# deadlock-reader.net
KiCad netlist of a schematic drawn in EAGLE
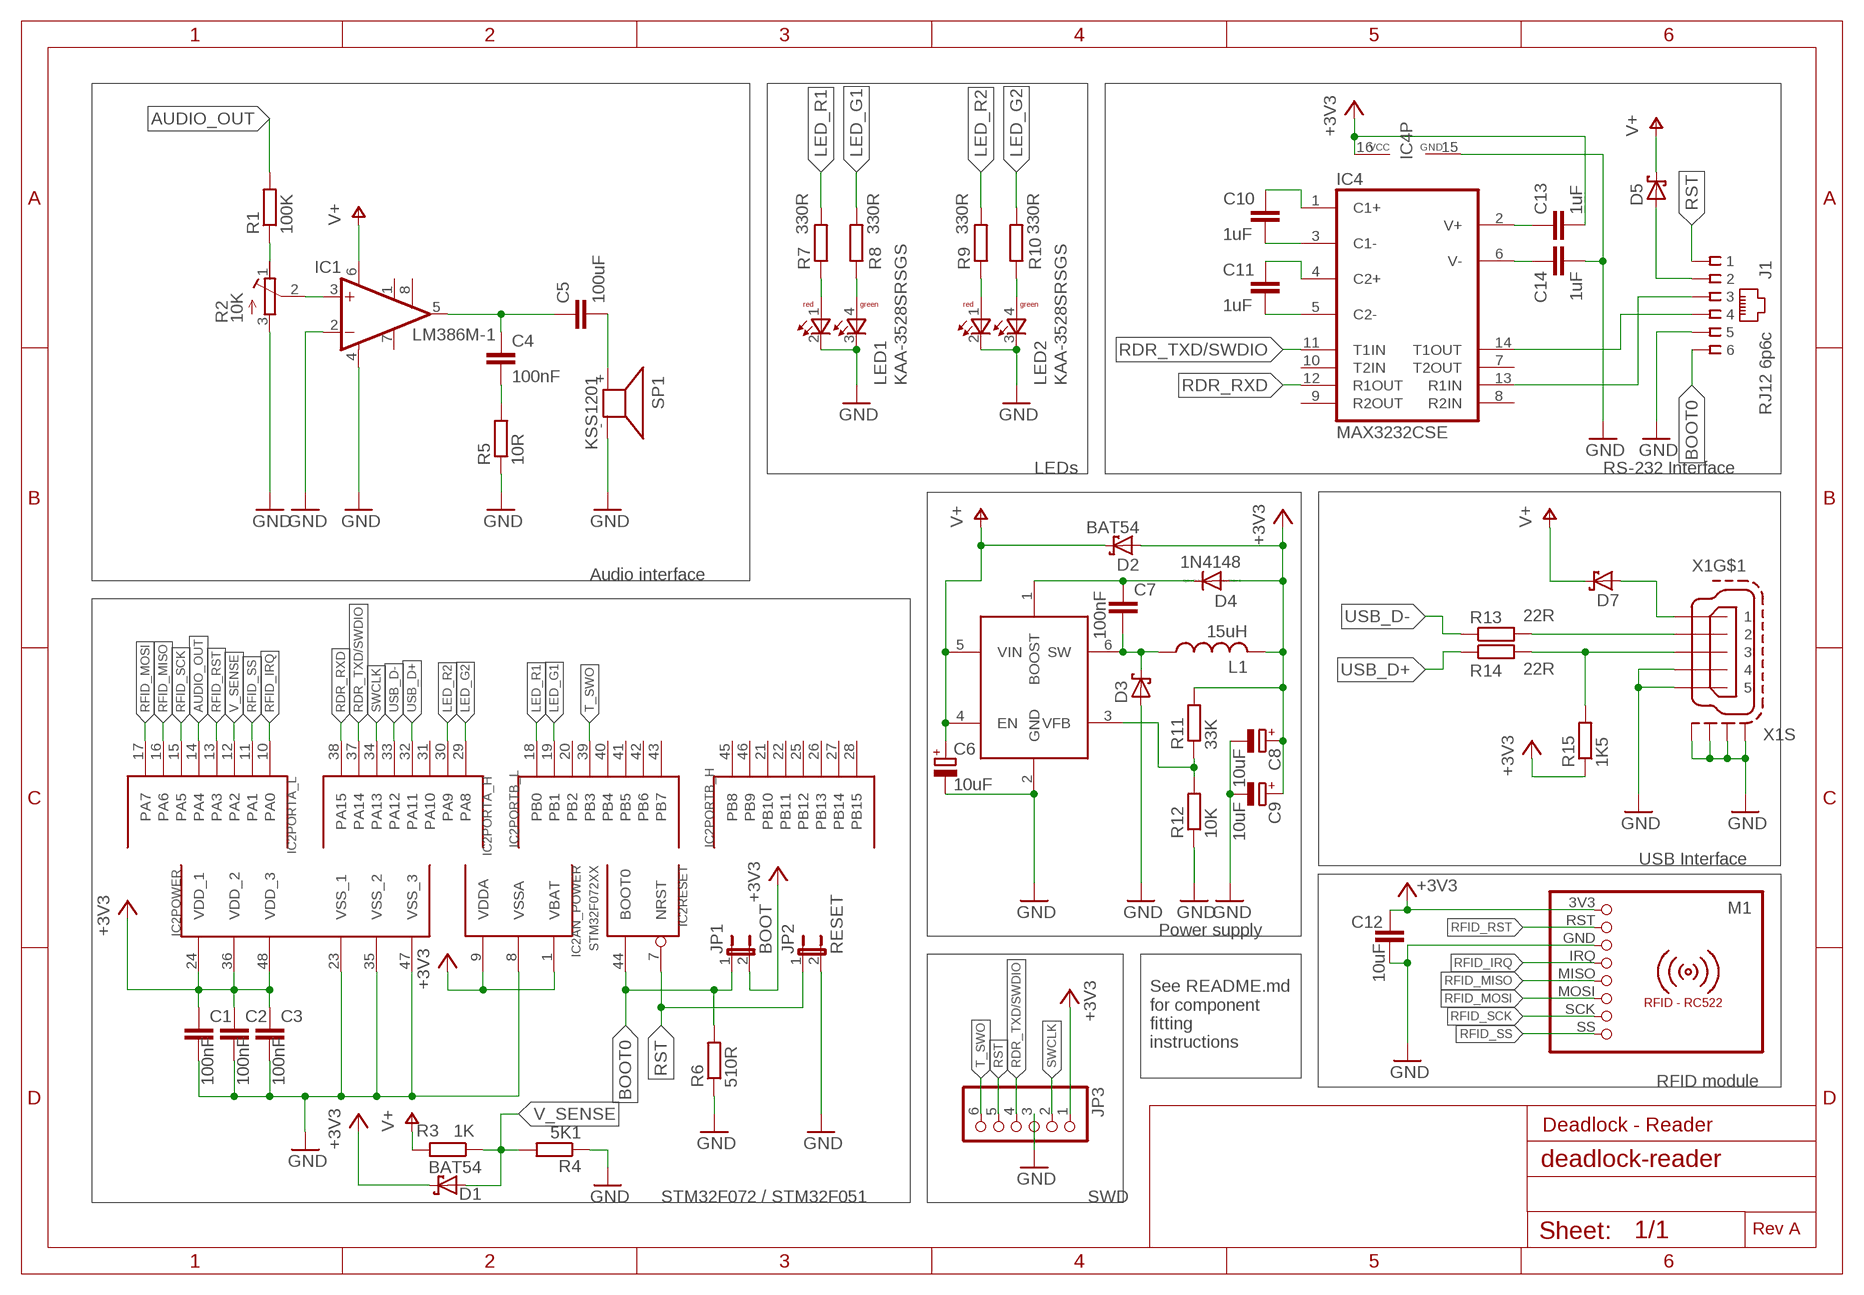
[diagram p0: schematic, sheet 1]

(export (version "E")
  (design (tool "Eeschema 10.0.6"))
  (components
    (comp (ref "C1")
      (value "100nF")
      (footprint "eagle-import:C0805")
      (libsource (lib "eagle-import") (part "C-EUC0805"))
    )
    (comp (ref "C2")
      (value "100nF")
      (footprint "eagle-import:C0805")
      (libsource (lib "eagle-import") (part "C-EUC0805"))
    )
    (comp (ref "C3")
      (value "100nF")
      (footprint "eagle-import:C0805")
      (libsource (lib "eagle-import") (part "C-EUC0805"))
    )
    (comp (ref "C4")
      (value "100nF")
      (footprint "eagle-import:C0805")
      (libsource (lib "eagle-import") (part "C-EUC0805"))
    )
    (comp (ref "C5")
      (value "100uF")
      (footprint "eagle-import:C1206")
      (libsource (lib "eagle-import") (part "C-EUC1206"))
    )
    (comp (ref "C6")
      (value "10uF")
      (footprint "eagle-import:SMC_D")
      (libsource (lib "eagle-import") (part "CPOL-EUSMCD"))
    )
    (comp (ref "C7")
      (value "100nF")
      (footprint "eagle-import:C0805")
      (libsource (lib "eagle-import") (part "C-EUC0805"))
    )
    (comp (ref "C8")
      (value "10uF")
      (footprint "eagle-import:A_3216-18R")
      (libsource (lib "eagle-import") (part "CPOL-EUA/3216-18R"))
    )
    (comp (ref "C9")
      (value "10uF")
      (footprint "eagle-import:A_3216-18R")
      (libsource (lib "eagle-import") (part "CPOL-EUA/3216-18R"))
    )
    (comp (ref "C10")
      (value "1uF")
      (footprint "eagle-import:C0805")
      (libsource (lib "eagle-import") (part "C-EUC0805"))
    )
    (comp (ref "C11")
      (value "1uF")
      (footprint "eagle-import:C0805")
      (libsource (lib "eagle-import") (part "C-EUC0805"))
    )
    (comp (ref "C12")
      (value "10uF")
      (footprint "eagle-import:C0805")
      (libsource (lib "eagle-import") (part "C-EUC0805"))
    )
    (comp (ref "C13")
      (value "1uF")
      (footprint "eagle-import:C0805")
      (libsource (lib "eagle-import") (part "C-EUC0805"))
    )
    (comp (ref "C14")
      (value "1uF")
      (footprint "eagle-import:C0805")
      (libsource (lib "eagle-import") (part "C-EUC0805"))
    )
    (comp (ref "D1")
      (value "BAT54")
      (footprint "eagle-import:SOT23")
      (libsource (lib "eagle-import") (part "BAT54"))
    )
    (comp (ref "D2")
      (value "BAT54")
      (footprint "eagle-import:SOT23")
      (libsource (lib "eagle-import") (part "BAT54"))
    )
    (comp (ref "D3")
      (value "BAT60J")
      (footprint "eagle-import:SOD323_ST")
      (libsource (lib "eagle-import") (part "BAT60J"))
    )
    (comp (ref "D4")
      (value "1N4148")
      (footprint "eagle-import:SOD323-W")
      (libsource (lib "eagle-import") (part "DIODE-SOD323-W"))
    )
    (comp (ref "D5")
      (value "BAT60J")
      (footprint "eagle-import:SOD323_ST")
      (libsource (lib "eagle-import") (part "BAT60J"))
    )
    (comp (ref "D7")
      (value "BAT60J")
      (footprint "eagle-import:SOD323_ST")
      (libsource (lib "eagle-import") (part "BAT60J"))
    )
    (comp (ref "IC1")
      (value "LM386M-1")
      (footprint "eagle-import:SO08")
      (libsource (lib "eagle-import") (part "LM386?-M1"))
    )
    (comp (ref "IC2")
      (value "STM32F072XX")
      (footprint "eagle-import:TQFP48")
      (libsource (lib "eagle-import") (part "STM32F072XX"))
    )
    (comp (ref "IC3")
      (value "MCP16301/H")
      (footprint "eagle-import:SOT23-6")
      (libsource (lib "eagle-import") (part "MCP16301/H"))
    )
    (comp (ref "IC4")
      (value "MAX3232CSE")
      (footprint "eagle-import:SO16")
      (libsource (lib "eagle-import") (part "MAX3232SEC"))
    )
    (comp (ref "J1")
      (value "RJ12 6p6c")
      (footprint "eagle-import:RJ11-NO_SHIELD")
      (libsource (lib "eagle-import") (part "RJ11-2X"))
    )
    (comp (ref "JP1")
      (value "BOOT")
      (footprint "eagle-import:JP1")
      (libsource (lib "eagle-import") (part "JP1E"))
    )
    (comp (ref "JP2")
      (value "RESET")
      (footprint "eagle-import:JP1")
      (libsource (lib "eagle-import") (part "JP1E"))
    )
    (comp (ref "JP3")
      (value "PINHD-1X6")
      (footprint "eagle-import:1X06")
      (libsource (lib "eagle-import") (part "PINHD-1X6"))
    )
    (comp (ref "L1")
      (value "15uH")
      (footprint "eagle-import:PIS2816")
      (libsource (lib "eagle-import") (part "L-USPIS2816"))
    )
    (comp (ref "LED1")
      (value "KAA-3528SRSGS")
      (footprint "eagle-import:KAA-3528SRSGS")
      (libsource (lib "eagle-import") (part "KAA-3528SRSGS"))
    )
    (comp (ref "LED2")
      (value "KAA-3528SRSGS")
      (footprint "eagle-import:KAA-3528SRSGS")
      (libsource (lib "eagle-import") (part "KAA-3528SRSGS"))
    )
    (comp (ref "M1")
      (value "RFID-RC522")
      (footprint "eagle-import:RFID-RC522")
      (libsource (lib "eagle-import") (part "RFID-RC522"))
    )
    (comp (ref "R1")
      (value "100K")
      (footprint "eagle-import:M0805")
      (libsource (lib "eagle-import") (part "resistor_R-EU_M0805"))
    )
    (comp (ref "R2")
      (value "10K")
      (footprint "eagle-import:RTRIM3314G")
      (libsource (lib "eagle-import") (part "R-TRIMM3314G"))
    )
    (comp (ref "R3")
      (value "1K")
      (footprint "eagle-import:R0805")
      (libsource (lib "eagle-import") (part "R-EU_R0805"))
    )
    (comp (ref "R4")
      (value "5K1")
      (footprint "eagle-import:R0805")
      (libsource (lib "eagle-import") (part "R-EU_R0805"))
    )
    (comp (ref "R5")
      (value "10R")
      (footprint "eagle-import:R0805")
      (libsource (lib "eagle-import") (part "R-EU_R0805"))
    )
    (comp (ref "R6")
      (value "510R")
      (footprint "eagle-import:R0805")
      (libsource (lib "eagle-import") (part "R-EU_R0805"))
    )
    (comp (ref "R7")
      (value "330R")
      (footprint "eagle-import:R0805")
      (libsource (lib "eagle-import") (part "R-EU_R0805"))
    )
    (comp (ref "R8")
      (value "330R")
      (footprint "eagle-import:R0805")
      (libsource (lib "eagle-import") (part "R-EU_R0805"))
    )
    (comp (ref "R9")
      (value "330R")
      (footprint "eagle-import:R0805")
      (libsource (lib "eagle-import") (part "R-EU_R0805"))
    )
    (comp (ref "R10")
      (value "330R")
      (footprint "eagle-import:R0805")
      (libsource (lib "eagle-import") (part "R-EU_R0805"))
    )
    (comp (ref "R11")
      (value "33K")
      (footprint "eagle-import:R0805")
      (libsource (lib "eagle-import") (part "R-EU_R0805"))
    )
    (comp (ref "R12")
      (value "10K")
      (footprint "eagle-import:R0805")
      (libsource (lib "eagle-import") (part "R-EU_R0805"))
    )
    (comp (ref "R13")
      (value "22R")
      (footprint "eagle-import:R0805")
      (libsource (lib "eagle-import") (part "R-EU_R0805"))
    )
    (comp (ref "R14")
      (value "22R")
      (footprint "eagle-import:R0805")
      (libsource (lib "eagle-import") (part "R-EU_R0805"))
    )
    (comp (ref "R15")
      (value "1K5")
      (footprint "eagle-import:R0805")
      (libsource (lib "eagle-import") (part "R-EU_R0805"))
    )
    (comp (ref "SP1")
      (value "KSS1201")
      (footprint "eagle-import:KSS1201")
      (libsource (lib "eagle-import") (part "KSS1201"))
    )
    (comp (ref "X1")
      (value "MINI-USB-SCHIELD-32005-301")
      (footprint "eagle-import:32005-301")
      (libsource (lib "eagle-import") (part "MINI-USB-SCHIELD-32005-301"))
    )
  )
  (nets
    (net (code "1") (name "+3V3") (class "Default")
      (node (ref "C1") (pin "1") (pinfunction "1_1") (pintype "passive"))
      (node (ref "C12") (pin "1") (pinfunction "1_1") (pintype "passive"))
      (node (ref "C13") (pin "2") (pinfunction "2_2") (pintype "passive"))
      (node (ref "C2") (pin "1") (pinfunction "1_1") (pintype "passive"))
      (node (ref "C3") (pin "1") (pinfunction "1_1") (pintype "passive"))
      (node (ref "C8") (pin "+") (pinfunction "+_+") (pintype "passive"))
      (node (ref "C9") (pin "+") (pinfunction "+_+") (pintype "passive"))
      (node (ref "D1") (pin "3") (pinfunction "C_3") (pintype "passive"))
      (node (ref "D2") (pin "1") (pinfunction "A_1") (pintype "passive"))
      (node (ref "D4") (pin "A") (pinfunction "A_A") (pintype "passive"))
      (node (ref "IC2") (pin "1") (pinfunction "VBAT_1") (pintype "power_in"))
      (node (ref "IC2") (pin "24") (pinfunction "VDD_1_24") (pintype "power_in"))
      (node (ref "IC2") (pin "36") (pinfunction "VDD_2_36") (pintype "power_in"))
      (node (ref "IC2") (pin "48") (pinfunction "VDD_3_48") (pintype "power_in"))
      (node (ref "IC2") (pin "9") (pinfunction "VDDA_9") (pintype "power_in"))
      (node (ref "IC4") (pin "16") (pinfunction "VCC_16") (pintype "power_in"))
      (node (ref "JP1") (pin "2") (pinfunction "2_2") (pintype "passive"))
      (node (ref "JP3") (pin "1") (pinfunction "1_1") (pintype "passive"))
      (node (ref "L1") (pin "2") (pinfunction "2_2") (pintype "passive"))
      (node (ref "M1") (pin "3V3") (pinfunction "1_3V3") (pintype "passive"))
      (node (ref "R11") (pin "2") (pinfunction "2_2") (pintype "passive"))
      (node (ref "R15") (pin "1") (pinfunction "1_1") (pintype "passive"))
    )
    (net (code "2") (name "AUDIO_OUT") (class "Default")
      (node (ref "IC2") (pin "14") (pinfunction "PA4_14") (pintype "bidirectional"))
      (node (ref "R1") (pin "2") (pinfunction "2_2") (pintype "passive"))
    )
    (net (code "3") (name "BOOT0") (class "Default")
      (node (ref "IC2") (pin "44") (pinfunction "BOOT0_44") (pintype "input"))
      (node (ref "J1") (pin "6") (pinfunction "6_6") (pintype "passive"))
      (node (ref "JP1") (pin "1") (pinfunction "1_1") (pintype "passive"))
      (node (ref "R6") (pin "2") (pinfunction "2_2") (pintype "passive"))
    )
    (net (code "4") (name "GND") (class "Default")
      (node (ref "C1") (pin "2") (pinfunction "2_2") (pintype "passive"))
      (node (ref "C12") (pin "2") (pinfunction "2_2") (pintype "passive"))
      (node (ref "C14") (pin "2") (pinfunction "2_2") (pintype "passive"))
      (node (ref "C2") (pin "2") (pinfunction "2_2") (pintype "passive"))
      (node (ref "C3") (pin "2") (pinfunction "2_2") (pintype "passive"))
      (node (ref "C6") (pin "-") (pinfunction "-_-") (pintype "passive"))
      (node (ref "C8") (pin "-") (pinfunction "-_-") (pintype "passive"))
      (node (ref "C9") (pin "-") (pinfunction "-_-") (pintype "passive"))
      (node (ref "D3") (pin "A") (pinfunction "A_A") (pintype "passive"))
      (node (ref "IC1") (pin "2") (pinfunction "-IN_2") (pintype "input"))
      (node (ref "IC1") (pin "4") (pinfunction "GND_4") (pintype "power_in"))
      (node (ref "IC2") (pin "23") (pinfunction "VSS_1_23") (pintype "power_in"))
      (node (ref "IC2") (pin "35") (pinfunction "VSS_2_35") (pintype "power_in"))
      (node (ref "IC2") (pin "47") (pinfunction "VSS_3_47") (pintype "power_in"))
      (node (ref "IC2") (pin "8") (pinfunction "VSSA_8") (pintype "power_in"))
      (node (ref "IC3") (pin "2") (pinfunction "GND_2") (pintype "power_in"))
      (node (ref "IC4") (pin "15") (pinfunction "GND_15") (pintype "power_in"))
      (node (ref "J1") (pin "5") (pinfunction "5_5") (pintype "passive"))
      (node (ref "JP2") (pin "2") (pinfunction "2_2") (pintype "passive"))
      (node (ref "JP3") (pin "3") (pinfunction "3_3") (pintype "passive"))
      (node (ref "LED1") (pin "2") (pinfunction "C-RED_2") (pintype "passive"))
      (node (ref "LED1") (pin "3") (pinfunction "C-GREEN_3") (pintype "passive"))
      (node (ref "LED2") (pin "2") (pinfunction "C-RED_2") (pintype "passive"))
      (node (ref "LED2") (pin "3") (pinfunction "C-GREEN_3") (pintype "passive"))
      (node (ref "M1") (pin "GND") (pinfunction "3_GND") (pintype "passive"))
      (node (ref "R12") (pin "1") (pinfunction "1_1") (pintype "passive"))
      (node (ref "R2") (pin "3") (pinfunction "A_3") (pintype "passive"))
      (node (ref "R4") (pin "1") (pinfunction "1_1") (pintype "passive"))
      (node (ref "R5") (pin "1") (pinfunction "1_1") (pintype "passive"))
      (node (ref "R6") (pin "1") (pinfunction "1_1") (pintype "passive"))
      (node (ref "SP1") (pin "-") (pinfunction "2_-") (pintype "passive"))
      (node (ref "X1") (pin "4") (pinfunction "4_4") (pintype "passive"))
      (node (ref "X1") (pin "5") (pinfunction "5_5") (pintype "passive"))
      (node (ref "X1") (pin "M1") (pinfunction "S1_M1") (pintype "passive"))
      (node (ref "X1") (pin "M2") (pinfunction "S2_M2") (pintype "passive"))
      (node (ref "X1") (pin "M3") (pinfunction "S3_M3") (pintype "passive"))
      (node (ref "X1") (pin "M4") (pinfunction "S4_M4") (pintype "passive"))
    )
    (net (code "5") (name "LED_G1") (class "Default")
      (node (ref "IC2") (pin "19") (pinfunction "PB1_19") (pintype "bidirectional"))
      (node (ref "R8") (pin "2") (pinfunction "2_2") (pintype "passive"))
    )
    (net (code "6") (name "LED_G2") (class "Default")
      (node (ref "IC2") (pin "29") (pinfunction "PA8_29") (pintype "bidirectional"))
      (node (ref "R10") (pin "2") (pinfunction "2_2") (pintype "passive"))
    )
    (net (code "7") (name "LED_R1") (class "Default")
      (node (ref "IC2") (pin "18") (pinfunction "PB0_18") (pintype "bidirectional"))
      (node (ref "R7") (pin "2") (pinfunction "2_2") (pintype "passive"))
    )
    (net (code "8") (name "LED_R2") (class "Default")
      (node (ref "IC2") (pin "30") (pinfunction "PA9_30") (pintype "bidirectional"))
      (node (ref "R9") (pin "2") (pinfunction "2_2") (pintype "passive"))
    )
    (net (code "9") (name "Net-(C4-Pad2)") (class "Default")
      (node (ref "C4") (pin "2") (pinfunction "2_2") (pintype "passive"))
      (node (ref "R5") (pin "2") (pinfunction "2_2") (pintype "passive"))
    )
    (net (code "10") (name "Net-(D5-PadA)") (class "Default")
      (node (ref "D5") (pin "A") (pinfunction "A_A") (pintype "passive"))
      (node (ref "J1") (pin "2") (pinfunction "2_2") (pintype "passive"))
    )
    (net (code "11") (name "Net-(D7-PadA)") (class "Default")
      (node (ref "D7") (pin "A") (pinfunction "A_A") (pintype "passive"))
      (node (ref "X1") (pin "1") (pinfunction "1_1") (pintype "passive"))
    )
    (net (code "12") (name "Net-(IC1-+IN)") (class "Default")
      (node (ref "IC1") (pin "3") (pinfunction "+IN_3") (pintype "input"))
      (node (ref "R2") (pin "2") (pinfunction "S_2") (pintype "passive"))
    )
    (net (code "13") (name "Net-(IC1-OUT)") (class "Default")
      (node (ref "C4") (pin "1") (pinfunction "1_1") (pintype "passive"))
      (node (ref "C5") (pin "1") (pinfunction "1_1") (pintype "passive"))
      (node (ref "IC1") (pin "5") (pinfunction "OUT_5") (pintype "output"))
    )
    (net (code "14") (name "Net-(IC3-BOOST)") (class "Default")
      (node (ref "C7") (pin "1") (pinfunction "1_1") (pintype "passive"))
      (node (ref "D4") (pin "C") (pinfunction "C_C") (pintype "passive"))
      (node (ref "IC3") (pin "1") (pinfunction "BOOST_1") (pintype "bidirectional"))
    )
    (net (code "15") (name "Net-(IC3-SW)") (class "Default")
      (node (ref "C7") (pin "2") (pinfunction "2_2") (pintype "passive"))
      (node (ref "D3") (pin "C") (pinfunction "C_C") (pintype "passive"))
      (node (ref "IC3") (pin "6") (pinfunction "SW_6") (pintype "power_in"))
      (node (ref "L1") (pin "1") (pinfunction "1_1") (pintype "passive"))
    )
    (net (code "16") (name "Net-(IC3-VFB)") (class "Default")
      (node (ref "IC3") (pin "3") (pinfunction "VFB_3") (pintype "bidirectional"))
      (node (ref "R11") (pin "1") (pinfunction "1_1") (pintype "passive"))
      (node (ref "R12") (pin "2") (pinfunction "2_2") (pintype "passive"))
    )
    (net (code "17") (name "Net-(IC4A-C1+)") (class "Default")
      (node (ref "C10") (pin "1") (pinfunction "1_1") (pintype "passive"))
      (node (ref "IC4") (pin "1") (pinfunction "C1+_1") (pintype "bidirectional"))
    )
    (net (code "18") (name "Net-(IC4A-C1-)") (class "Default")
      (node (ref "C10") (pin "2") (pinfunction "2_2") (pintype "passive"))
      (node (ref "IC4") (pin "3") (pinfunction "C1-_3") (pintype "bidirectional"))
    )
    (net (code "19") (name "Net-(IC4A-C2+)") (class "Default")
      (node (ref "C11") (pin "1") (pinfunction "1_1") (pintype "passive"))
      (node (ref "IC4") (pin "4") (pinfunction "C2+_4") (pintype "bidirectional"))
    )
    (net (code "20") (name "Net-(IC4A-C2-)") (class "Default")
      (node (ref "C11") (pin "2") (pinfunction "2_2") (pintype "passive"))
      (node (ref "IC4") (pin "5") (pinfunction "C2-_5") (pintype "bidirectional"))
    )
    (net (code "21") (name "Net-(IC4A-R1IN)") (class "Default")
      (node (ref "IC4") (pin "13") (pinfunction "R1IN_13") (pintype "input"))
      (node (ref "J1") (pin "3") (pinfunction "3_3") (pintype "passive"))
    )
    (net (code "22") (name "Net-(IC4A-T1OUT)") (class "Default")
      (node (ref "IC4") (pin "14") (pinfunction "T1OUT_14") (pintype "output"))
      (node (ref "J1") (pin "4") (pinfunction "4_4") (pintype "passive"))
    )
    (net (code "23") (name "Net-(IC4A-V+)") (class "Default")
      (node (ref "C13") (pin "1") (pinfunction "1_1") (pintype "passive"))
      (node (ref "IC4") (pin "2") (pinfunction "V+_2") (pintype "bidirectional"))
    )
    (net (code "24") (name "Net-(IC4A-V-)") (class "Default")
      (node (ref "C14") (pin "1") (pinfunction "1_1") (pintype "passive"))
      (node (ref "IC4") (pin "6") (pinfunction "V-_6") (pintype "bidirectional"))
    )
    (net (code "25") (name "Net-(LED1-A-GREEN)") (class "Default")
      (node (ref "LED1") (pin "4") (pinfunction "A-GREEN_4") (pintype "passive"))
      (node (ref "R8") (pin "1") (pinfunction "1_1") (pintype "passive"))
    )
    (net (code "26") (name "Net-(LED1-A-RED)") (class "Default")
      (node (ref "LED1") (pin "1") (pinfunction "A-RED_1") (pintype "passive"))
      (node (ref "R7") (pin "1") (pinfunction "1_1") (pintype "passive"))
    )
    (net (code "27") (name "Net-(LED2-A-GREEN)") (class "Default")
      (node (ref "LED2") (pin "4") (pinfunction "A-GREEN_4") (pintype "passive"))
      (node (ref "R10") (pin "1") (pinfunction "1_1") (pintype "passive"))
    )
    (net (code "28") (name "Net-(LED2-A-RED)") (class "Default")
      (node (ref "LED2") (pin "1") (pinfunction "A-RED_1") (pintype "passive"))
      (node (ref "R9") (pin "1") (pinfunction "1_1") (pintype "passive"))
    )
    (net (code "29") (name "Net-(R2-E)") (class "Default")
      (node (ref "R1") (pin "1") (pinfunction "1_1") (pintype "passive"))
      (node (ref "R2") (pin "1") (pinfunction "E_1") (pintype "passive"))
    )
    (net (code "30") (name "Net-(R13-Pad2)") (class "Default")
      (node (ref "R13") (pin "2") (pinfunction "2_2") (pintype "passive"))
      (node (ref "X1") (pin "2") (pinfunction "2_2") (pintype "passive"))
    )
    (net (code "31") (name "Net-(R14-Pad2)") (class "Default")
      (node (ref "R14") (pin "2") (pinfunction "2_2") (pintype "passive"))
      (node (ref "R15") (pin "2") (pinfunction "2_2") (pintype "passive"))
      (node (ref "X1") (pin "3") (pinfunction "3_3") (pintype "passive"))
    )
    (net (code "32") (name "Net-(SP1-1)") (class "Default")
      (node (ref "C5") (pin "2") (pinfunction "2_2") (pintype "passive"))
      (node (ref "SP1") (pin "+") (pinfunction "1_+") (pintype "passive"))
    )
    (net (code "33") (name "RDR_RXD") (class "Default")
      (node (ref "IC2") (pin "38") (pinfunction "PA15_38") (pintype "bidirectional"))
      (node (ref "IC4") (pin "12") (pinfunction "R1OUT_12") (pintype "output"))
    )
    (net (code "34") (name "RDR_TXD{slash}SWDIO") (class "Default")
      (node (ref "IC2") (pin "37") (pinfunction "PA14_37") (pintype "bidirectional"))
      (node (ref "IC4") (pin "11") (pinfunction "T1IN_11") (pintype "input"))
      (node (ref "JP3") (pin "4") (pinfunction "4_4") (pintype "passive"))
    )
    (net (code "35") (name "RFID_IRQ") (class "Default")
      (node (ref "IC2") (pin "10") (pinfunction "PA0_10") (pintype "bidirectional"))
      (node (ref "M1") (pin "IRQ") (pinfunction "4_IRQ") (pintype "passive"))
    )
    (net (code "36") (name "RFID_MISO") (class "Default")
      (node (ref "IC2") (pin "16") (pinfunction "PA6_16") (pintype "bidirectional"))
      (node (ref "M1") (pin "MISO") (pinfunction "5_MISO") (pintype "passive"))
    )
    (net (code "37") (name "RFID_MOSI") (class "Default")
      (node (ref "IC2") (pin "17") (pinfunction "PA7_17") (pintype "bidirectional"))
      (node (ref "M1") (pin "MOSI") (pinfunction "6_MOSI") (pintype "passive"))
    )
    (net (code "38") (name "RFID_RST") (class "Default")
      (node (ref "IC2") (pin "13") (pinfunction "PA3_13") (pintype "bidirectional"))
      (node (ref "M1") (pin "RST") (pinfunction "2_RST") (pintype "passive"))
    )
    (net (code "39") (name "RFID_SCK") (class "Default")
      (node (ref "IC2") (pin "15") (pinfunction "PA5_15") (pintype "bidirectional"))
      (node (ref "M1") (pin "SCK") (pinfunction "7_SCK") (pintype "passive"))
    )
    (net (code "40") (name "RFID_SS") (class "Default")
      (node (ref "IC2") (pin "11") (pinfunction "PA1_11") (pintype "bidirectional"))
      (node (ref "M1") (pin "SS") (pinfunction "8_SS") (pintype "passive"))
    )
    (net (code "41") (name "RST") (class "Default")
      (node (ref "IC2") (pin "7") (pinfunction "NRST_7") (pintype "input"))
      (node (ref "J1") (pin "1") (pinfunction "1_1") (pintype "passive"))
      (node (ref "JP2") (pin "1") (pinfunction "1_1") (pintype "passive"))
      (node (ref "JP3") (pin "5") (pinfunction "5_5") (pintype "passive"))
    )
    (net (code "42") (name "SWCLK") (class "Default")
      (node (ref "IC2") (pin "34") (pinfunction "PA13_34") (pintype "bidirectional"))
      (node (ref "JP3") (pin "2") (pinfunction "2_2") (pintype "passive"))
    )
    (net (code "43") (name "T_SWO") (class "Default")
      (node (ref "IC2") (pin "39") (pinfunction "PB3_39") (pintype "bidirectional"))
      (node (ref "JP3") (pin "6") (pinfunction "6_6") (pintype "passive"))
    )
    (net (code "44") (name "USB_D+") (class "Default")
      (node (ref "IC2") (pin "32") (pinfunction "PA11_32") (pintype "bidirectional"))
      (node (ref "R14") (pin "1") (pinfunction "1_1") (pintype "passive"))
    )
    (net (code "45") (name "USB_D-") (class "Default")
      (node (ref "IC2") (pin "33") (pinfunction "PA12_33") (pintype "bidirectional"))
      (node (ref "R13") (pin "1") (pinfunction "1_1") (pintype "passive"))
    )
    (net (code "46") (name "V+") (class "Default")
      (node (ref "C6") (pin "+") (pinfunction "+_+") (pintype "passive"))
      (node (ref "D2") (pin "3") (pinfunction "C_3") (pintype "passive"))
      (node (ref "D5") (pin "C") (pinfunction "C_C") (pintype "passive"))
      (node (ref "D7") (pin "C") (pinfunction "C_C") (pintype "passive"))
      (node (ref "IC1") (pin "6") (pinfunction "VS_6") (pintype "power_in"))
      (node (ref "IC3") (pin "4") (pinfunction "EN_4") (pintype "bidirectional"))
      (node (ref "IC3") (pin "5") (pinfunction "VIN_5") (pintype "power_in"))
      (node (ref "R3") (pin "2") (pinfunction "2_2") (pintype "passive"))
    )
    (net (code "47") (name "V_SENSE") (class "Default")
      (node (ref "D1") (pin "1") (pinfunction "A_1") (pintype "passive"))
      (node (ref "IC2") (pin "12") (pinfunction "PA2_12") (pintype "bidirectional"))
      (node (ref "R3") (pin "1") (pinfunction "1_1") (pintype "passive"))
      (node (ref "R4") (pin "2") (pinfunction "2_2") (pintype "passive"))
    )
    (net (code "48") (name "unconnected-(IC1-BYPASS-Pad7)") (class "Default")
      (node (ref "IC1") (pin "7") (pinfunction "BYPASS_7") (pintype "passive"))
    )
    (net (code "49") (name "unconnected-(IC1-GAIN-Pad1)") (class "Default")
      (node (ref "IC1") (pin "1") (pinfunction "GAIN_1") (pintype "passive"))
    )
    (net (code "50") (name "unconnected-(IC1-GAIN-Pad8)") (class "Default")
      (node (ref "IC1") (pin "8") (pinfunction "GAIN_8") (pintype "passive"))
    )
    (net (code "51") (name "unconnected-(IC2B-PA10-Pad31)") (class "Default")
      (node (ref "IC2") (pin "31") (pinfunction "PA10_31") (pintype "bidirectional"))
    )
    (net (code "52") (name "unconnected-(IC2D-PB8-Pad45)") (class "Default")
      (node (ref "IC2") (pin "45") (pinfunction "PB8_45") (pintype "bidirectional"))
    )
    (net (code "53") (name "unconnected-(IC2D-PB9-Pad46)") (class "Default")
      (node (ref "IC2") (pin "46") (pinfunction "PB9_46") (pintype "bidirectional"))
    )
    (net (code "54") (name "unconnected-(IC2D-PB10-Pad21)") (class "Default")
      (node (ref "IC2") (pin "21") (pinfunction "PB10_21") (pintype "bidirectional"))
    )
    (net (code "55") (name "unconnected-(IC2D-PB11-Pad22)") (class "Default")
      (node (ref "IC2") (pin "22") (pinfunction "PB11_22") (pintype "bidirectional"))
    )
    (net (code "56") (name "unconnected-(IC2D-PB12-Pad25)") (class "Default")
      (node (ref "IC2") (pin "25") (pinfunction "PB12_25") (pintype "bidirectional"))
    )
    (net (code "57") (name "unconnected-(IC2D-PB13-Pad26)") (class "Default")
      (node (ref "IC2") (pin "26") (pinfunction "PB13_26") (pintype "bidirectional"))
    )
    (net (code "58") (name "unconnected-(IC2D-PB14-Pad27)") (class "Default")
      (node (ref "IC2") (pin "27") (pinfunction "PB14_27") (pintype "bidirectional"))
    )
    (net (code "59") (name "unconnected-(IC2D-PB15-Pad28)") (class "Default")
      (node (ref "IC2") (pin "28") (pinfunction "PB15_28") (pintype "bidirectional"))
    )
    (net (code "60") (name "unconnected-(IC2E-PB2-Pad20)") (class "Default")
      (node (ref "IC2") (pin "20") (pinfunction "PB2_20") (pintype "bidirectional"))
    )
    (net (code "61") (name "unconnected-(IC2E-PB4-Pad40)") (class "Default")
      (node (ref "IC2") (pin "40") (pinfunction "PB4_40") (pintype "bidirectional"))
    )
    (net (code "62") (name "unconnected-(IC2E-PB5-Pad41)") (class "Default")
      (node (ref "IC2") (pin "41") (pinfunction "PB5_41") (pintype "bidirectional"))
    )
    (net (code "63") (name "unconnected-(IC2E-PB6-Pad42)") (class "Default")
      (node (ref "IC2") (pin "42") (pinfunction "PB6_42") (pintype "bidirectional"))
    )
    (net (code "64") (name "unconnected-(IC2E-PB7-Pad43)") (class "Default")
      (node (ref "IC2") (pin "43") (pinfunction "PB7_43") (pintype "bidirectional"))
    )
    (net (code "65") (name "unconnected-(IC4A-R2IN-Pad8)") (class "Default")
      (node (ref "IC4") (pin "8") (pinfunction "R2IN_8") (pintype "input"))
    )
    (net (code "66") (name "unconnected-(IC4A-R2OUT-Pad9)") (class "Default")
      (node (ref "IC4") (pin "9") (pinfunction "R2OUT_9") (pintype "output"))
    )
    (net (code "67") (name "unconnected-(IC4A-T2IN-Pad10)") (class "Default")
      (node (ref "IC4") (pin "10") (pinfunction "T2IN_10") (pintype "input"))
    )
    (net (code "68") (name "unconnected-(IC4A-T2OUT-Pad7)") (class "Default")
      (node (ref "IC4") (pin "7") (pinfunction "T2OUT_7") (pintype "output"))
    )
  )
)
